# IR_Schreib_Lesekopf_TTL_Neu_V1.net
KiCad netlist of a schematic drawn in EAGLE
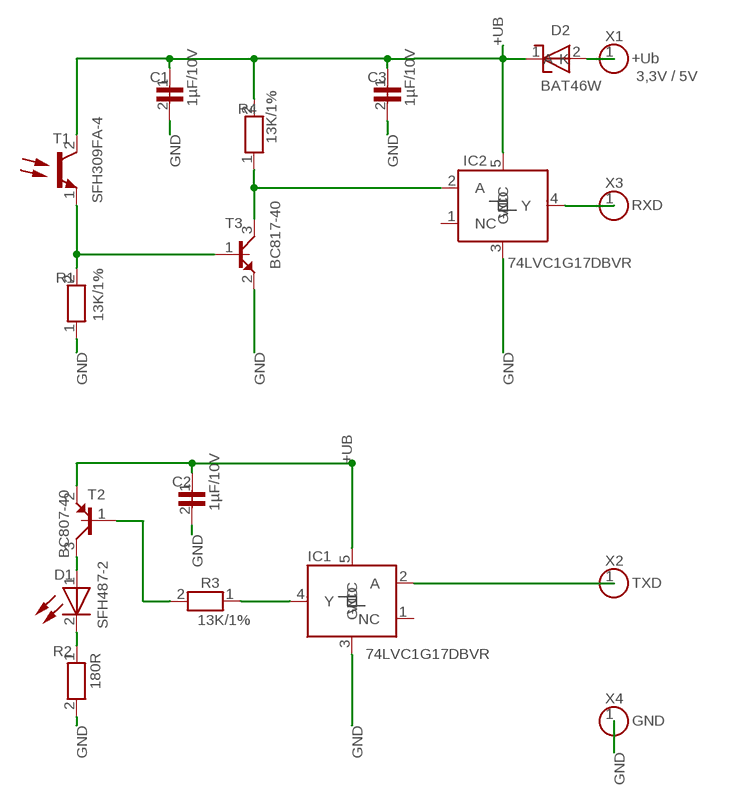
[diagram p0: schematic, sheet 1]

(export (version "E")
  (design (tool "Eeschema 10.0.6"))
  (components
    (comp (ref "C1")
      (value "1µF/10V")
      (footprint "eagle-import:0805_11")
      (libsource (lib "eagle-import") (part "C_KERAMIK_0,1µF_0805_11"))
    )
    (comp (ref "C2")
      (value "1µF/10V")
      (footprint "eagle-import:0805_21")
      (libsource (lib "eagle-import") (part "C_KERAMIK_0,1µF_0805_21"))
    )
    (comp (ref "C3")
      (value "1µF/10V")
      (footprint "eagle-import:0805_10")
      (libsource (lib "eagle-import") (part "C_KERAMIK_0,1µF_0805_10"))
    )
    (comp (ref "D1")
      (value "SFH487-2")
      (footprint "eagle-import:LED_3MM_13")
      (libsource (lib "eagle-import") (part "CN304_13"))
    )
    (comp (ref "D2")
      (value "BAT46W")
      (footprint "eagle-import:SOD123_25")
      (libsource (lib "eagle-import") (part "BAT46_DIN_25"))
    )
    (comp (ref "IC1")
      (value "74LVC1G17DBVR")
      (footprint "eagle-import:SOT23_5_20")
      (libsource (lib "eagle-import") (part "74LVC1G86DBVRG4_20"))
    )
    (comp (ref "IC2")
      (value "74LVC1G17DBVR")
      (footprint "eagle-import:SOT23_5_23")
      (libsource (lib "eagle-import") (part "74LVC1G86DBVRG4_23"))
    )
    (comp (ref "R1")
      (value "13K/1%")
      (footprint "eagle-import:0805_5")
      (libsource (lib "eagle-import") (part "R-0805_5"))
    )
    (comp (ref "R2")
      (value "180R")
      (footprint "eagle-import:0805_27")
      (libsource (lib "eagle-import") (part "R-0805_27"))
    )
    (comp (ref "R3")
      (value "13K/1%")
      (footprint "eagle-import:0805_14")
      (libsource (lib "eagle-import") (part "R-0805_14"))
    )
    (comp (ref "R4")
      (value "13K/1%")
      (footprint "eagle-import:0805_6")
      (libsource (lib "eagle-import") (part "R-0805_6"))
    )
    (comp (ref "T1")
      (value "SFH309FA-4")
      (footprint "eagle-import:FOTO_4MM_4")
      (libsource (lib "eagle-import") (part "SFH309-4_4"))
    )
    (comp (ref "T2")
      (value "BC807-40")
      (footprint "eagle-import:SOT23_3_28")
      (libsource (lib "eagle-import") (part "BC807-40_28"))
    )
    (comp (ref "T3")
      (value "BC817-40")
      (footprint "eagle-import:SOT23_3_26")
      (libsource (lib "eagle-import") (part "BC817_26"))
    )
    (comp (ref "X1")
      (value "+Ub")
      (footprint "eagle-import:LOETPUNKT_3")
      (libsource (lib "eagle-import") (part "LOETPUNKT_3"))
    )
    (comp (ref "X2")
      (value "TXD")
      (footprint "eagle-import:LOETPUNKT_19")
      (libsource (lib "eagle-import") (part "LOETPUNKT_19"))
    )
    (comp (ref "X3")
      (value "RXD")
      (footprint "eagle-import:LOETPUNKT_2")
      (libsource (lib "eagle-import") (part "LOETPUNKT_2"))
    )
    (comp (ref "X4")
      (value "GND")
      (footprint "eagle-import:LOETPUNKT_1")
      (libsource (lib "eagle-import") (part "LOETPUNKT_1"))
    )
  )
  (nets
    (net (code "1") (name "/+UB") (class "Default")
      (node (ref "C1") (pin "1") (pinfunction "1_1") (pintype "passive"))
      (node (ref "C2") (pin "1") (pinfunction "1_1") (pintype "passive"))
      (node (ref "C3") (pin "1") (pinfunction "1_1") (pintype "passive"))
      (node (ref "D2") (pin "1") (pinfunction "K_1") (pintype "passive"))
      (node (ref "IC1") (pin "5") (pinfunction "VCC_5") (pintype "passive"))
      (node (ref "IC2") (pin "5") (pinfunction "VCC_5") (pintype "passive"))
      (node (ref "R4") (pin "2") (pinfunction "2_2") (pintype "passive"))
      (node (ref "T1") (pin "2") (pinfunction "2_2") (pintype "passive"))
      (node (ref "T2") (pin "2") (pinfunction "2_2") (pintype "passive"))
    )
    (net (code "2") (name "/GND") (class "Default")
      (node (ref "C1") (pin "2") (pinfunction "2_2") (pintype "passive"))
      (node (ref "C2") (pin "2") (pinfunction "2_2") (pintype "passive"))
      (node (ref "C3") (pin "2") (pinfunction "2_2") (pintype "passive"))
      (node (ref "IC1") (pin "3") (pinfunction "GND_3") (pintype "passive"))
      (node (ref "IC2") (pin "3") (pinfunction "GND_3") (pintype "passive"))
      (node (ref "R1") (pin "1") (pinfunction "1_1") (pintype "passive"))
      (node (ref "R2") (pin "2") (pinfunction "2_2") (pintype "passive"))
      (node (ref "T3") (pin "2") (pinfunction "2_2") (pintype "passive"))
      (node (ref "X4") (pin "1") (pinfunction "1_1") (pintype "passive"))
    )
    (net (code "3") (name "Net-(D1-Pad1)") (class "Default")
      (node (ref "D1") (pin "1") (pinfunction "1_1") (pintype "passive"))
      (node (ref "T2") (pin "3") (pinfunction "3_3") (pintype "passive"))
    )
    (net (code "4") (name "Net-(D1-Pad2)") (class "Default")
      (node (ref "D1") (pin "2") (pinfunction "2_2") (pintype "passive"))
      (node (ref "R2") (pin "1") (pinfunction "1_1") (pintype "passive"))
    )
    (net (code "5") (name "Net-(D2-A)") (class "Default")
      (node (ref "D2") (pin "2") (pinfunction "A_2") (pintype "passive"))
      (node (ref "X1") (pin "1") (pinfunction "1_1") (pintype "passive"))
    )
    (net (code "6") (name "Net-(IC1-A)") (class "Default")
      (node (ref "IC1") (pin "2") (pinfunction "A_2") (pintype "passive"))
      (node (ref "X2") (pin "1") (pinfunction "1_1") (pintype "passive"))
    )
    (net (code "7") (name "Net-(IC1-Y)") (class "Default")
      (node (ref "IC1") (pin "4") (pinfunction "Y_4") (pintype "passive"))
      (node (ref "R3") (pin "1") (pinfunction "1_1") (pintype "passive"))
    )
    (net (code "8") (name "Net-(IC2-A)") (class "Default")
      (node (ref "IC2") (pin "2") (pinfunction "A_2") (pintype "passive"))
      (node (ref "R4") (pin "1") (pinfunction "1_1") (pintype "passive"))
      (node (ref "T3") (pin "3") (pinfunction "3_3") (pintype "passive"))
    )
    (net (code "9") (name "Net-(IC2-Y)") (class "Default")
      (node (ref "IC2") (pin "4") (pinfunction "Y_4") (pintype "passive"))
      (node (ref "X3") (pin "1") (pinfunction "1_1") (pintype "passive"))
    )
    (net (code "10") (name "Net-(R1-Pad2)") (class "Default")
      (node (ref "R1") (pin "2") (pinfunction "2_2") (pintype "passive"))
      (node (ref "T1") (pin "1") (pinfunction "1_1") (pintype "passive"))
      (node (ref "T3") (pin "1") (pinfunction "1_1") (pintype "passive"))
    )
    (net (code "11") (name "Net-(R3-Pad2)") (class "Default")
      (node (ref "R3") (pin "2") (pinfunction "2_2") (pintype "passive"))
      (node (ref "T2") (pin "1") (pinfunction "1_1") (pintype "passive"))
    )
    (net (code "12") (name "unconnected-(IC1-NC-Pad1)") (class "Default")
      (node (ref "IC1") (pin "1") (pinfunction "NC_1") (pintype "passive"))
    )
    (net (code "13") (name "unconnected-(IC2-NC-Pad1)") (class "Default")
      (node (ref "IC2") (pin "1") (pinfunction "NC_1") (pintype "passive"))
    )
  )
)
